# SAMV71_Xplained_Ultra_Memory.net
KiCad netlist of a schematic drawn in Altium Designer
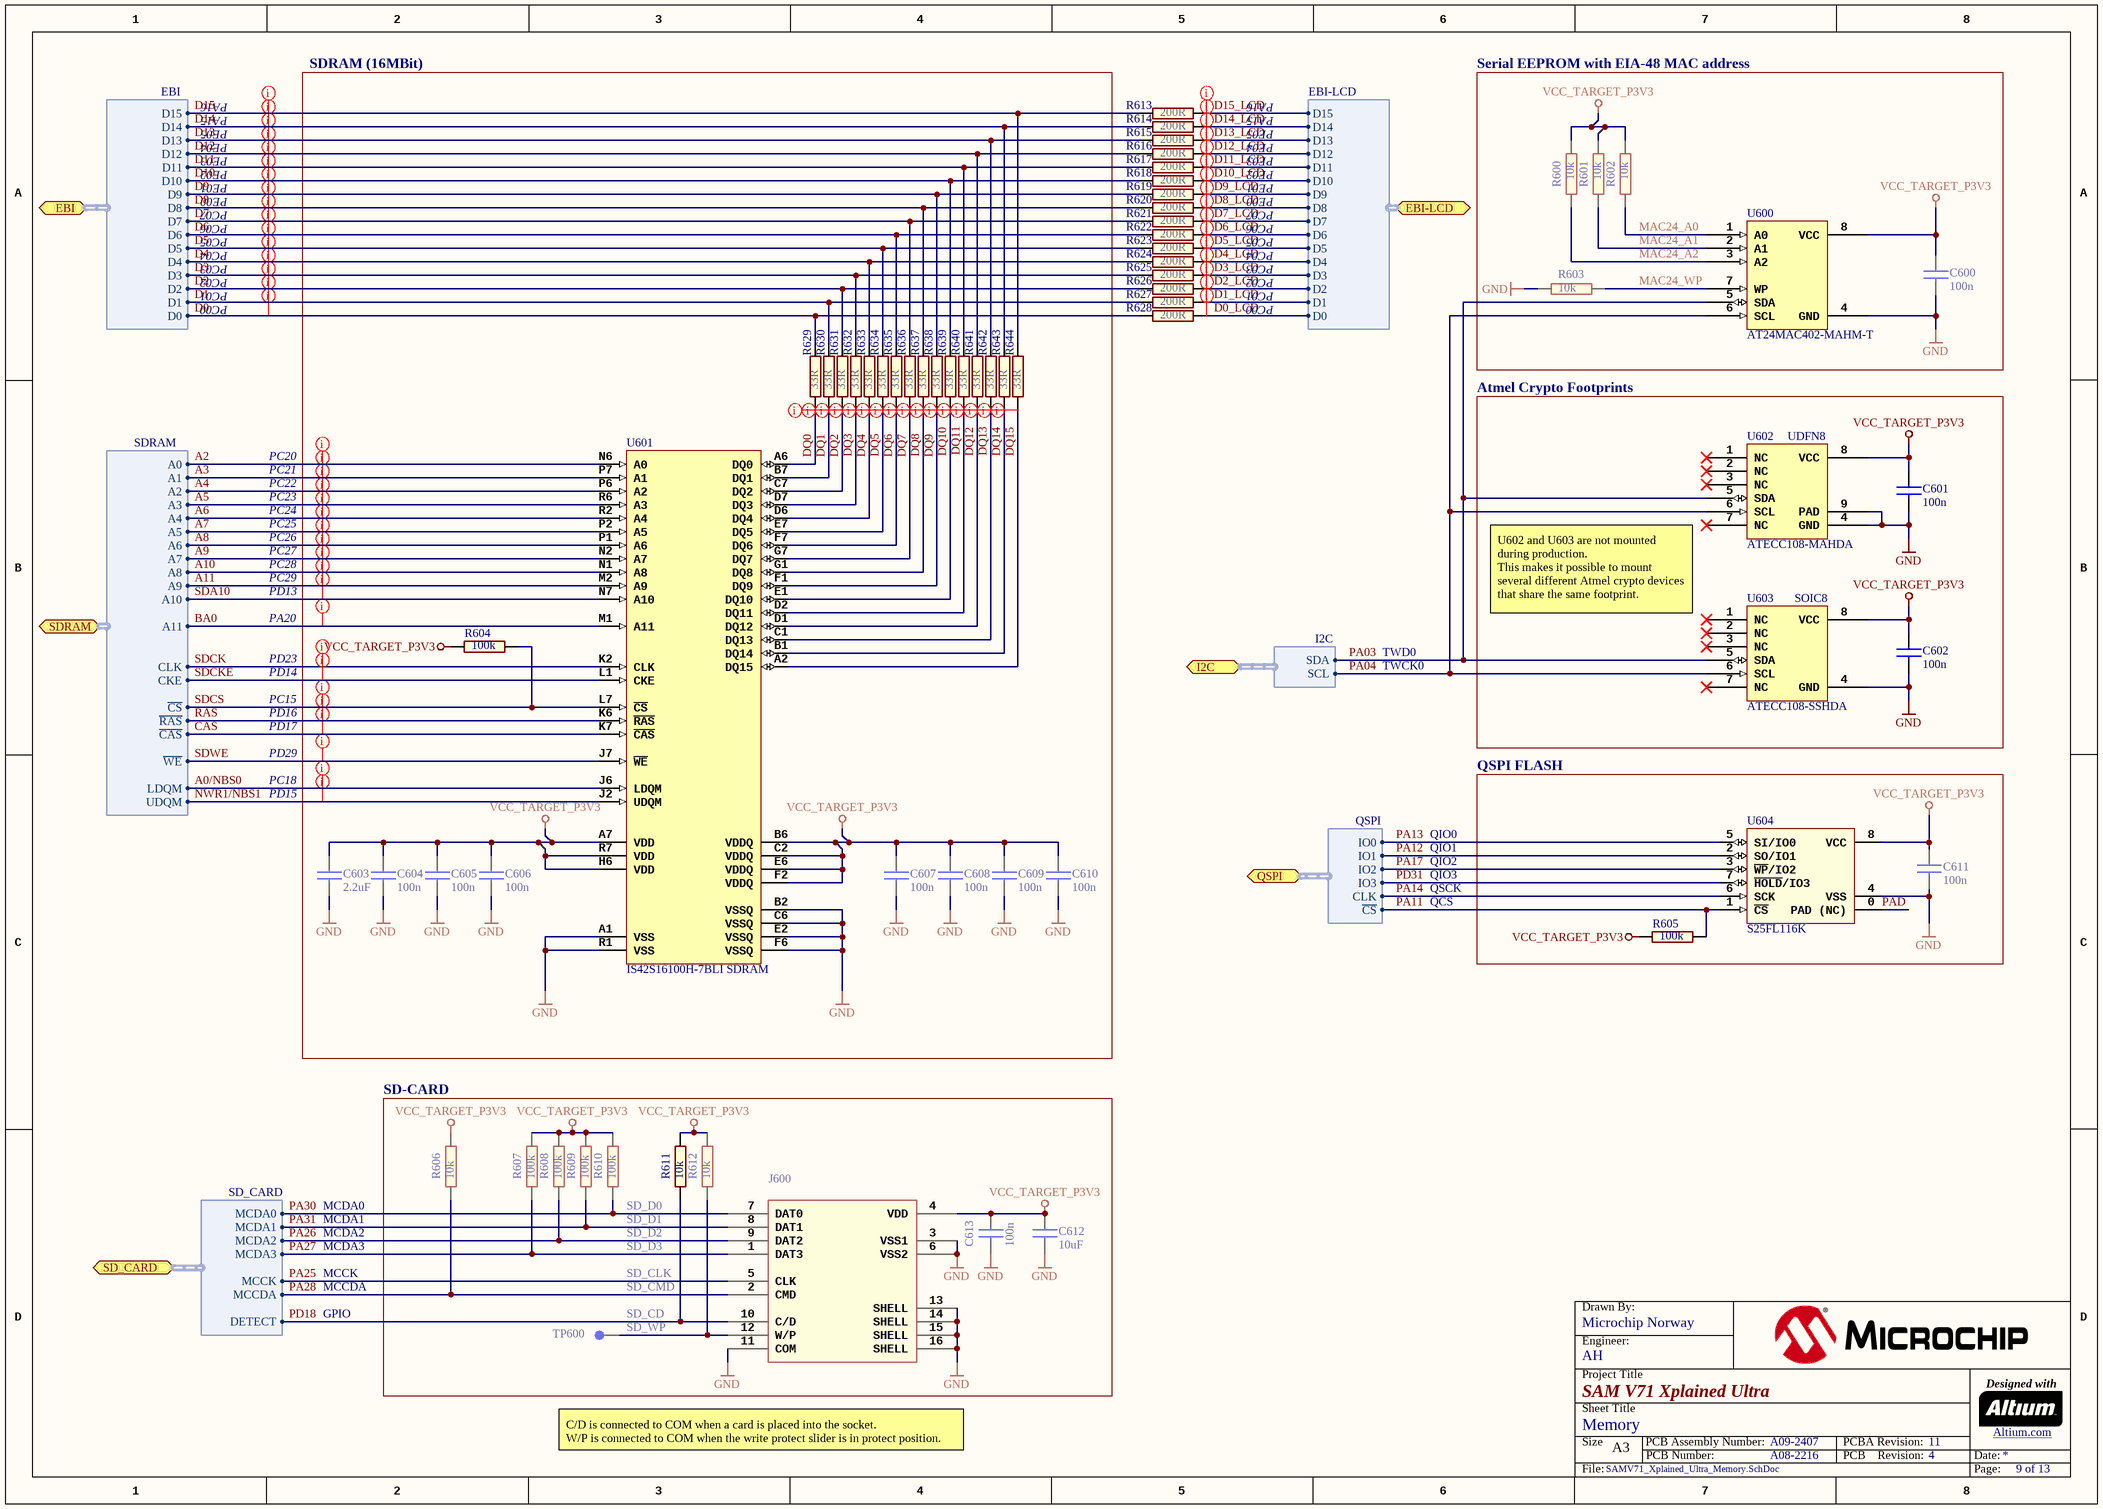
[diagram p0: SAMV71_Xplained_Ultra_Memory.SchDoc]

(export (version "E")
  (design (tool "Eeschema 10.0.6"))
  (components
    (comp (ref "C600")
      (value "100n")
      (footprint "AP1-00001")
      (description "Ceramic capacitor, SMD 0402, X7R, 16V, +/-10%")
      (fields (field (name "TOLERANCE") "16V, +/-10%") (field (name "MANUFACTURER") "Kemet"))
      (libsource (lib "AltiumDbLib") (part "CAP-NONPOL"))
    )
    (comp (ref "C601")
      (value "100n")
      (footprint "AP1-00001")
      (description "Ceramic capacitor, SMD 0402, X7R, 16V, +/-10%")
      (fields (field (name "TOLERANCE") "16V, +/-10%") (field (name "MANUFACTURER") "Kemet"))
      (libsource (lib "AltiumDbLib") (part "CAP-NONPOL"))
    )
    (comp (ref "C602")
      (value "100n")
      (footprint "AP1-00001")
      (description "Ceramic capacitor, SMD 0402, X7R, 16V, +/-10%")
      (fields (field (name "TOLERANCE") "16V, +/-10%") (field (name "MANUFACTURER") "Kemet"))
      (libsource (lib "AltiumDbLib") (part "CAP-NONPOL"))
    )
    (comp (ref "C603")
      (value "2.2uF")
      (footprint "AP1-00053")
      (description "Ceramic capacitor, SMD 0402, X5R, 6.3V, +/-20%")
      (fields (field (name "TOLERANCE") "Â±20%") (field (name "MANUFACTURER") "Kemet"))
      (libsource (lib "AltiumDbLib") (part "CAP-NONPOL"))
    )
    (comp (ref "C604")
      (value "100n")
      (footprint "AP1-00053")
      (description "Ceramic capacitor, SMD 0402, X7R, 16V, +/-10%")
      (fields (field (name "TOLERANCE") "16V, +/-10%") (field (name "MANUFACTURER") "Kemet"))
      (libsource (lib "AltiumDbLib") (part "CAP-NONPOL"))
    )
    (comp (ref "C605")
      (value "100n")
      (footprint "AP1-00053")
      (description "Ceramic capacitor, SMD 0402, X7R, 16V, +/-10%")
      (fields (field (name "TOLERANCE") "16V, +/-10%") (field (name "MANUFACTURER") "Kemet"))
      (libsource (lib "AltiumDbLib") (part "CAP-NONPOL"))
    )
    (comp (ref "C606")
      (value "100n")
      (footprint "AP1-00053")
      (description "Ceramic capacitor, SMD 0402, X7R, 16V, +/-10%")
      (fields (field (name "TOLERANCE") "16V, +/-10%") (field (name "MANUFACTURER") "Kemet"))
      (libsource (lib "AltiumDbLib") (part "CAP-NONPOL"))
    )
    (comp (ref "C607")
      (value "100n")
      (footprint "AP1-00053")
      (description "Ceramic capacitor, SMD 0402, X7R, 16V, +/-10%")
      (fields (field (name "TOLERANCE") "16V, +/-10%") (field (name "MANUFACTURER") "Kemet"))
      (libsource (lib "AltiumDbLib") (part "CAP-NONPOL"))
    )
    (comp (ref "C608")
      (value "100n")
      (footprint "AP1-00053")
      (description "Ceramic capacitor, SMD 0402, X7R, 16V, +/-10%")
      (fields (field (name "TOLERANCE") "16V, +/-10%") (field (name "MANUFACTURER") "Kemet"))
      (libsource (lib "AltiumDbLib") (part "CAP-NONPOL"))
    )
    (comp (ref "C609")
      (value "100n")
      (footprint "AP1-00053")
      (description "Ceramic capacitor, SMD 0402, X7R, 16V, +/-10%")
      (fields (field (name "TOLERANCE") "16V, +/-10%") (field (name "MANUFACTURER") "Kemet"))
      (libsource (lib "AltiumDbLib") (part "CAP-NONPOL"))
    )
    (comp (ref "C610")
      (value "100n")
      (footprint "AP1-00053")
      (description "Ceramic capacitor, SMD 0402, X7R, 16V, +/-10%")
      (fields (field (name "TOLERANCE") "16V, +/-10%") (field (name "MANUFACTURER") "Kemet"))
      (libsource (lib "AltiumDbLib") (part "CAP-NONPOL"))
    )
    (comp (ref "C611")
      (value "100n")
      (footprint "AP1-00001")
      (description "Ceramic capacitor, SMD 0402, X7R, 16V, +/-10%")
      (fields (field (name "TOLERANCE") "16V, +/-10%") (field (name "MANUFACTURER") "Kemet"))
      (libsource (lib "AltiumDbLib") (part "CAP-NONPOL"))
    )
    (comp (ref "C612")
      (value "10uF")
      (footprint "AP1-00041")
      (description "Ceramic capacitor, SMD 0805, X5R, 10V, 10 %, (de19441)")
      (fields (field (name "TOLERANCE") "10%") (field (name "MANUFACTURER") "Murata"))
      (libsource (lib "AltiumDbLib") (part "CAP-NONPOL"))
    )
    (comp (ref "C613")
      (value "100n")
      (footprint "AP1-00001")
      (description "Ceramic capacitor, SMD 0402, X7R, 16V, +/-10%")
      (fields (field (name "TOLERANCE") "16V, +/-10%") (field (name "MANUFACTURER") "Kemet"))
      (libsource (lib "AltiumDbLib") (part "CAP-NONPOL"))
    )
    (comp (ref "J600")
      (value "~")
      (footprint "AP8-00377")
      (description "SD/MMC socket, 2.7mm, push-push, SMD")
      (fields
        (field (name "MANUFACTURER") "Kyocera-elco")
        (field (name "MPN") "KYOCERA - 14 5738 009 220 859+")
      )
      (libsource (lib "AltiumDbLib") (part "SD_MMC"))
    )
    (comp (ref "R600")
      (value "10k")
      (footprint "AP2-00000")
      (description "Thick film resistor, SMD 0402, 1/16W, 1%")
      (fields (field (name "TOLERANCE") "1 %") (field (name "MANUFACTURER") "vishay"))
      (libsource (lib "AltiumDbLib") (part "R2"))
    )
    (comp (ref "R601")
      (value "10k")
      (footprint "AP2-00000")
      (description "Thick film resistor, SMD 0402, 1/16W, 1%")
      (fields (field (name "TOLERANCE") "1 %") (field (name "MANUFACTURER") "vishay"))
      (libsource (lib "AltiumDbLib") (part "R2"))
    )
    (comp (ref "R602")
      (value "10k")
      (footprint "AP2-00000")
      (description "Thick film resistor, SMD 0402, 1/16W, 1%")
      (fields (field (name "TOLERANCE") "1 %") (field (name "MANUFACTURER") "vishay"))
      (libsource (lib "AltiumDbLib") (part "R2"))
    )
    (comp (ref "R603")
      (value "10k")
      (footprint "AP2-00000")
      (description "Thick film resistor, SMD 0402, 1/16W, 1%")
      (fields (field (name "TOLERANCE") "1 %") (field (name "MANUFACTURER") "vishay"))
      (libsource (lib "") (part "R2_1"))
    )
    (comp (ref "R604")
      (value "100k")
      (footprint "AP2-00000")
      (description "Thick film resistor, SMD 0402, 1/16W, 1%")
      (fields (field (name "TOLERANCE") "1 %") (field (name "MANUFACTURER") "ASJ"))
      (libsource (lib "") (part "R2_1"))
    )
    (comp (ref "R605")
      (value "100k")
      (footprint "AP2-00000")
      (description "Thick film resistor, SMD 0402, 1/16W, 1%")
      (fields (field (name "TOLERANCE") "1 %") (field (name "MANUFACTURER") "ASJ"))
      (libsource (lib "") (part "R2_1"))
    )
    (comp (ref "R606")
      (value "10k")
      (footprint "AP2-00000")
      (description "Thick film resistor, SMD 0402, 1/16W, 1%")
      (fields (field (name "TOLERANCE") "1 %") (field (name "MANUFACTURER") "vishay"))
      (libsource (lib "AltiumDbLib") (part "R2"))
    )
    (comp (ref "R607")
      (value "100k")
      (footprint "AP2-00000")
      (description "Thick film resistor, SMD 0402, 1/16W, 1%")
      (fields (field (name "TOLERANCE") "1 %") (field (name "MANUFACTURER") "ASJ"))
      (libsource (lib "AltiumDbLib") (part "R2"))
    )
    (comp (ref "R608")
      (value "100k")
      (footprint "AP2-00000")
      (description "Thick film resistor, SMD 0402, 1/16W, 1%")
      (fields (field (name "TOLERANCE") "1 %") (field (name "MANUFACTURER") "ASJ"))
      (libsource (lib "AltiumDbLib") (part "R2"))
    )
    (comp (ref "R609")
      (value "100k")
      (footprint "AP2-00000")
      (description "Thick film resistor, SMD 0402, 1/16W, 1%")
      (fields (field (name "TOLERANCE") "1 %") (field (name "MANUFACTURER") "ASJ"))
      (libsource (lib "AltiumDbLib") (part "R2"))
    )
    (comp (ref "R610")
      (value "100k")
      (footprint "AP2-00000")
      (description "Thick film resistor, SMD 0402, 1/16W, 1%")
      (fields (field (name "TOLERANCE") "1 %") (field (name "MANUFACTURER") "ASJ"))
      (libsource (lib "AltiumDbLib") (part "R2"))
    )
    (comp (ref "R611")
      (value "10k")
      (footprint "AP2-00000")
      (description "Thick film resistor, SMD 0402, 1/16W, 1%")
      (fields (field (name "TOLERANCE") "1 %") (field (name "MANUFACTURER") "vishay"))
      (libsource (lib "AltiumDbLib") (part "R2"))
    )
    (comp (ref "R612")
      (value "10k")
      (footprint "AP2-00000")
      (description "Thick film resistor, SMD 0402, 1/16W, 1%")
      (fields (field (name "TOLERANCE") "1 %") (field (name "MANUFACTURER") "vishay"))
      (libsource (lib "AltiumDbLib") (part "R2"))
    )
    (comp (ref "R613")
      (value "200R")
      (footprint "AP2-00011")
      (description "Thick film resistor, SMD 0402, 1/16W, 1%")
      (fields (field (name "TOLERANCE") "1 %"))
      (libsource (lib "") (part "R2_3"))
    )
    (comp (ref "R614")
      (value "200R")
      (footprint "AP2-00011")
      (description "Thick film resistor, SMD 0402, 1/16W, 1%")
      (fields (field (name "TOLERANCE") "1 %"))
      (libsource (lib "") (part "R2_3"))
    )
    (comp (ref "R615")
      (value "200R")
      (footprint "AP2-00011")
      (description "Thick film resistor, SMD 0402, 1/16W, 1%")
      (fields (field (name "TOLERANCE") "1 %"))
      (libsource (lib "") (part "R2_3"))
    )
    (comp (ref "R616")
      (value "200R")
      (footprint "AP2-00011")
      (description "Thick film resistor, SMD 0402, 1/16W, 1%")
      (fields (field (name "TOLERANCE") "1 %"))
      (libsource (lib "") (part "R2_3"))
    )
    (comp (ref "R617")
      (value "200R")
      (footprint "AP2-00011")
      (description "Thick film resistor, SMD 0402, 1/16W, 1%")
      (fields (field (name "TOLERANCE") "1 %"))
      (libsource (lib "") (part "R2_3"))
    )
    (comp (ref "R618")
      (value "200R")
      (footprint "AP2-00011")
      (description "Thick film resistor, SMD 0402, 1/16W, 1%")
      (fields (field (name "TOLERANCE") "1 %"))
      (libsource (lib "") (part "R2_3"))
    )
    (comp (ref "R619")
      (value "200R")
      (footprint "AP2-00011")
      (description "Thick film resistor, SMD 0402, 1/16W, 1%")
      (fields (field (name "TOLERANCE") "1 %"))
      (libsource (lib "") (part "R2_3"))
    )
    (comp (ref "R620")
      (value "200R")
      (footprint "AP2-00011")
      (description "Thick film resistor, SMD 0402, 1/16W, 1%")
      (fields (field (name "TOLERANCE") "1 %"))
      (libsource (lib "") (part "R2_3"))
    )
    (comp (ref "R621")
      (value "200R")
      (footprint "AP2-00011")
      (description "Thick film resistor, SMD 0402, 1/16W, 1%")
      (fields (field (name "TOLERANCE") "1 %"))
      (libsource (lib "") (part "R2_3"))
    )
    (comp (ref "R622")
      (value "200R")
      (footprint "AP2-00011")
      (description "Thick film resistor, SMD 0402, 1/16W, 1%")
      (fields (field (name "TOLERANCE") "1 %"))
      (libsource (lib "") (part "R2_3"))
    )
    (comp (ref "R623")
      (value "200R")
      (footprint "AP2-00011")
      (description "Thick film resistor, SMD 0402, 1/16W, 1%")
      (fields (field (name "TOLERANCE") "1 %"))
      (libsource (lib "") (part "R2_3"))
    )
    (comp (ref "R624")
      (value "200R")
      (footprint "AP2-00011")
      (description "Thick film resistor, SMD 0402, 1/16W, 1%")
      (fields (field (name "TOLERANCE") "1 %"))
      (libsource (lib "") (part "R2_3"))
    )
    (comp (ref "R625")
      (value "200R")
      (footprint "AP2-00011")
      (description "Thick film resistor, SMD 0402, 1/16W, 1%")
      (fields (field (name "TOLERANCE") "1 %"))
      (libsource (lib "") (part "R2_3"))
    )
    (comp (ref "R626")
      (value "200R")
      (footprint "AP2-00011")
      (description "Thick film resistor, SMD 0402, 1/16W, 1%")
      (fields (field (name "TOLERANCE") "1 %"))
      (libsource (lib "") (part "R2_3"))
    )
    (comp (ref "R627")
      (value "200R")
      (footprint "AP2-00011")
      (description "Thick film resistor, SMD 0402, 1/16W, 1%")
      (fields (field (name "TOLERANCE") "1 %"))
      (libsource (lib "") (part "R2_3"))
    )
    (comp (ref "R628")
      (value "200R")
      (footprint "AP2-00011")
      (description "Thick film resistor, SMD 0402, 1/16W, 1%")
      (fields (field (name "TOLERANCE") "1 %"))
      (libsource (lib "") (part "R2_3"))
    )
    (comp (ref "R629")
      (value "33R")
      (footprint "AP2-00011")
      (description "Thick film resistor, SMD 0402, 1/16W, 1%")
      (fields (field (name "TOLERANCE") "1 %") (field (name "MANUFACTURER") "ASJ"))
      (libsource (lib "") (part "R2_2"))
    )
    (comp (ref "R630")
      (value "33R")
      (footprint "AP2-00011")
      (description "Thick film resistor, SMD 0402, 1/16W, 1%")
      (fields (field (name "TOLERANCE") "1 %") (field (name "MANUFACTURER") "ASJ"))
      (libsource (lib "") (part "R2_2"))
    )
    (comp (ref "R631")
      (value "33R")
      (footprint "AP2-00011")
      (description "Thick film resistor, SMD 0402, 1/16W, 1%")
      (fields (field (name "TOLERANCE") "1 %") (field (name "MANUFACTURER") "ASJ"))
      (libsource (lib "") (part "R2_2"))
    )
    (comp (ref "R632")
      (value "33R")
      (footprint "AP2-00011")
      (description "Thick film resistor, SMD 0402, 1/16W, 1%")
      (fields (field (name "TOLERANCE") "1 %") (field (name "MANUFACTURER") "ASJ"))
      (libsource (lib "") (part "R2_2"))
    )
    (comp (ref "R633")
      (value "33R")
      (footprint "AP2-00011")
      (description "Thick film resistor, SMD 0402, 1/16W, 1%")
      (fields (field (name "TOLERANCE") "1 %") (field (name "MANUFACTURER") "ASJ"))
      (libsource (lib "") (part "R2_2"))
    )
    (comp (ref "R634")
      (value "33R")
      (footprint "AP2-00011")
      (description "Thick film resistor, SMD 0402, 1/16W, 1%")
      (fields (field (name "TOLERANCE") "1 %") (field (name "MANUFACTURER") "ASJ"))
      (libsource (lib "") (part "R2_2"))
    )
    (comp (ref "R635")
      (value "33R")
      (footprint "AP2-00011")
      (description "Thick film resistor, SMD 0402, 1/16W, 1%")
      (fields (field (name "TOLERANCE") "1 %") (field (name "MANUFACTURER") "ASJ"))
      (libsource (lib "") (part "R2_2"))
    )
    (comp (ref "R636")
      (value "33R")
      (footprint "AP2-00011")
      (description "Thick film resistor, SMD 0402, 1/16W, 1%")
      (fields (field (name "TOLERANCE") "1 %") (field (name "MANUFACTURER") "ASJ"))
      (libsource (lib "") (part "R2_2"))
    )
    (comp (ref "R637")
      (value "33R")
      (footprint "AP2-00011")
      (description "Thick film resistor, SMD 0402, 1/16W, 1%")
      (fields (field (name "TOLERANCE") "1 %") (field (name "MANUFACTURER") "ASJ"))
      (libsource (lib "") (part "R2_2"))
    )
    (comp (ref "R638")
      (value "33R")
      (footprint "AP2-00011")
      (description "Thick film resistor, SMD 0402, 1/16W, 1%")
      (fields (field (name "TOLERANCE") "1 %") (field (name "MANUFACTURER") "ASJ"))
      (libsource (lib "") (part "R2_2"))
    )
    (comp (ref "R639")
      (value "33R")
      (footprint "AP2-00011")
      (description "Thick film resistor, SMD 0402, 1/16W, 1%")
      (fields (field (name "TOLERANCE") "1 %") (field (name "MANUFACTURER") "ASJ"))
      (libsource (lib "") (part "R2_2"))
    )
    (comp (ref "R640")
      (value "33R")
      (footprint "AP2-00011")
      (description "Thick film resistor, SMD 0402, 1/16W, 1%")
      (fields (field (name "TOLERANCE") "1 %") (field (name "MANUFACTURER") "ASJ"))
      (libsource (lib "") (part "R2_2"))
    )
    (comp (ref "R641")
      (value "33R")
      (footprint "AP2-00011")
      (description "Thick film resistor, SMD 0402, 1/16W, 1%")
      (fields (field (name "TOLERANCE") "1 %") (field (name "MANUFACTURER") "ASJ"))
      (libsource (lib "") (part "R2_2"))
    )
    (comp (ref "R642")
      (value "33R")
      (footprint "AP2-00011")
      (description "Thick film resistor, SMD 0402, 1/16W, 1%")
      (fields (field (name "TOLERANCE") "1 %") (field (name "MANUFACTURER") "ASJ"))
      (libsource (lib "") (part "R2_2"))
    )
    (comp (ref "R643")
      (value "33R")
      (footprint "AP2-00011")
      (description "Thick film resistor, SMD 0402, 1/16W, 1%")
      (fields (field (name "TOLERANCE") "1 %") (field (name "MANUFACTURER") "ASJ"))
      (libsource (lib "") (part "R2_2"))
    )
    (comp (ref "R644")
      (value "33R")
      (footprint "AP2-00011")
      (description "Thick film resistor, SMD 0402, 1/16W, 1%")
      (fields (field (name "TOLERANCE") "1 %") (field (name "MANUFACTURER") "ASJ"))
      (libsource (lib "") (part "R2_2"))
    )
    (comp (ref "TP600")
      (value "~")
      (footprint "AP8-00010")
      (description "Single SMD testpad")
      (libsource (lib "AltiumDbLib") (part "TESTPOINT"))
    )
    (comp (ref "U600")
      (value "AT24MAC402-MAHM-T")
      (footprint "AP6-00186")
      (description "2kbit I2C EEPROM, single EUI-48 MAC, 1.7-5.5V, 2x3mm UDFN (8MA2)")
      (fields (field (name "MANUFACTURER") "ATMEL"))
      (libsource (lib "AltiumDbLib") (part "AT24MAC-8PIN"))
    )
    (comp (ref "U601")
      (value "IS42S16100H-7BLI SDRAM")
      (footprint "AP6-00400")
      (description "16Mbit  SDRAM (512K Words x 16 Bits x 2 Banks), 143 MHz 3,3V")
      (fields (field (name "MANUFACTURER") "ISSI") (field (name "MPN") "IS42S16100H-7BLI"))
      (libsource (lib "AltiumDbLib") (part "IS42S16100E"))
    )
    (comp (ref "U602")
      (value "ATECC108-MAHDA")
      (footprint "AP6-00409")
      (description "Secure authentication and product validation device, EEPROM, I2C, 2.0 - 5.5V, UDFN8")
      (fields (field (name "MANUFACTURER") "ATMEL") (field (name "MPN") "ATECC108-MAHDA-T"))
      (libsource (lib "AltiumDbLib") (part "ATECC108_UDFN"))
    )
    (comp (ref "U603")
      (value "ATECC108-SSHDA")
      (footprint "AP6-00071")
      (description "Secure authentication and product validation device, EEPROM, I2C, 2.0 - 5.5V, SOIC8")
      (fields (field (name "MANUFACTURER") "ATMEL") (field (name "MPN") "ATECC108-SSHDA-T"))
      (libsource (lib "AltiumDbLib") (part "ATECC108_SOIC"))
    )
    (comp (ref "U604")
      (value "S25FL116K")
      (footprint "AP6-00402")
      (description "16 Mbit (2MB) SPI Quad I/O flash, 3.3V, 108MHz, WSON-8, industrial temperature")
      (fields (field (name "MANUFACTURER") "Spansion") (field (name "MPN") "S25FL116K0XNFI013"))
      (libsource (lib "AltiumDbLib") (part "S25FL1"))
    )
  )
  (nets
    (net (code "7") (name "/A0{slash}NBS0") (class "Default")
      (node (ref "U601") (pin "J6") (pinfunction "LDQM_J6") (pintype "input"))
    )
    (net (code "8") (name "/A2") (class "Default")
      (node (ref "U601") (pin "N6") (pinfunction "A0_N6") (pintype "input"))
    )
    (net (code "9") (name "/A3") (class "Default")
      (node (ref "U601") (pin "P7") (pinfunction "A1_P7") (pintype "input"))
    )
    (net (code "10") (name "/A4") (class "Default")
      (node (ref "U601") (pin "P6") (pinfunction "A2_P6") (pintype "input"))
    )
    (net (code "11") (name "/A5") (class "Default")
      (node (ref "U601") (pin "R6") (pinfunction "A3_R6") (pintype "input"))
    )
    (net (code "12") (name "/A6") (class "Default")
      (node (ref "U601") (pin "R2") (pinfunction "A4_R2") (pintype "input"))
    )
    (net (code "13") (name "/A7") (class "Default")
      (node (ref "U601") (pin "P2") (pinfunction "A5_P2") (pintype "input"))
    )
    (net (code "14") (name "/A8") (class "Default")
      (node (ref "U601") (pin "P1") (pinfunction "A6_P1") (pintype "input"))
    )
    (net (code "15") (name "/A9") (class "Default")
      (node (ref "U601") (pin "N2") (pinfunction "A7_N2") (pintype "input"))
    )
    (net (code "16") (name "/A10") (class "Default")
      (node (ref "U601") (pin "N1") (pinfunction "A8_N1") (pintype "input"))
    )
    (net (code "17") (name "/A11") (class "Default")
      (node (ref "U601") (pin "M2") (pinfunction "A9_M2") (pintype "input"))
    )
    (net (code "18") (name "/BA0") (class "Default")
      (node (ref "U601") (pin "M1") (pinfunction "A11_M1") (pintype "input"))
    )
    (net (code "19") (name "/CAS") (class "Default")
      (node (ref "U601") (pin "K7") (pinfunction "~{CAS}_K7") (pintype "input"))
    )
    (net (code "20") (name "/D0") (class "Default")
      (node (ref "R628") (pin "2") (pinfunction "2_2") (pintype "passive"))
      (node (ref "R629") (pin "1") (pinfunction "1_1") (pintype "passive"))
    )
    (net (code "21") (name "/D0_LCD") (class "Default")
      (node (ref "R628") (pin "1") (pinfunction "1_1") (pintype "passive"))
    )
    (net (code "22") (name "/D1") (class "Default")
      (node (ref "R627") (pin "2") (pinfunction "2_2") (pintype "passive"))
      (node (ref "R630") (pin "1") (pinfunction "1_1") (pintype "passive"))
    )
    (net (code "23") (name "/D1_LCD") (class "Default")
      (node (ref "R627") (pin "1") (pinfunction "1_1") (pintype "passive"))
    )
    (net (code "24") (name "/D2") (class "Default")
      (node (ref "R626") (pin "2") (pinfunction "2_2") (pintype "passive"))
      (node (ref "R631") (pin "1") (pinfunction "1_1") (pintype "passive"))
    )
    (net (code "25") (name "/D2_LCD") (class "Default")
      (node (ref "R626") (pin "1") (pinfunction "1_1") (pintype "passive"))
    )
    (net (code "26") (name "/D3") (class "Default")
      (node (ref "R625") (pin "2") (pinfunction "2_2") (pintype "passive"))
      (node (ref "R632") (pin "1") (pinfunction "1_1") (pintype "passive"))
    )
    (net (code "27") (name "/D3_LCD") (class "Default")
      (node (ref "R625") (pin "1") (pinfunction "1_1") (pintype "passive"))
    )
    (net (code "28") (name "/D4") (class "Default")
      (node (ref "R624") (pin "2") (pinfunction "2_2") (pintype "passive"))
      (node (ref "R633") (pin "1") (pinfunction "1_1") (pintype "passive"))
    )
    (net (code "29") (name "/D4_LCD") (class "Default")
      (node (ref "R624") (pin "1") (pinfunction "1_1") (pintype "passive"))
    )
    (net (code "30") (name "/D5") (class "Default")
      (node (ref "R623") (pin "2") (pinfunction "2_2") (pintype "passive"))
      (node (ref "R634") (pin "1") (pinfunction "1_1") (pintype "passive"))
    )
    (net (code "31") (name "/D5_LCD") (class "Default")
      (node (ref "R623") (pin "1") (pinfunction "1_1") (pintype "passive"))
    )
    (net (code "32") (name "/D6") (class "Default")
      (node (ref "R622") (pin "2") (pinfunction "2_2") (pintype "passive"))
      (node (ref "R635") (pin "1") (pinfunction "1_1") (pintype "passive"))
    )
    (net (code "33") (name "/D6_LCD") (class "Default")
      (node (ref "R622") (pin "1") (pinfunction "1_1") (pintype "passive"))
    )
    (net (code "34") (name "/D7") (class "Default")
      (node (ref "R621") (pin "2") (pinfunction "2_2") (pintype "passive"))
      (node (ref "R636") (pin "1") (pinfunction "1_1") (pintype "passive"))
    )
    (net (code "35") (name "/D7_LCD") (class "Default")
      (node (ref "R621") (pin "1") (pinfunction "1_1") (pintype "passive"))
    )
    (net (code "36") (name "/D8") (class "Default")
      (node (ref "R620") (pin "2") (pinfunction "2_2") (pintype "passive"))
      (node (ref "R637") (pin "1") (pinfunction "1_1") (pintype "passive"))
    )
    (net (code "37") (name "/D8_LCD") (class "Default")
      (node (ref "R620") (pin "1") (pinfunction "1_1") (pintype "passive"))
    )
    (net (code "38") (name "/D9") (class "Default")
      (node (ref "R619") (pin "2") (pinfunction "2_2") (pintype "passive"))
      (node (ref "R638") (pin "1") (pinfunction "1_1") (pintype "passive"))
    )
    (net (code "39") (name "/D9_LCD") (class "Default")
      (node (ref "R619") (pin "1") (pinfunction "1_1") (pintype "passive"))
    )
    (net (code "40") (name "/D10") (class "Default")
      (node (ref "R618") (pin "2") (pinfunction "2_2") (pintype "passive"))
      (node (ref "R639") (pin "1") (pinfunction "1_1") (pintype "passive"))
    )
    (net (code "41") (name "/D10_LCD") (class "Default")
      (node (ref "R618") (pin "1") (pinfunction "1_1") (pintype "passive"))
    )
    (net (code "42") (name "/D11") (class "Default")
      (node (ref "R617") (pin "2") (pinfunction "2_2") (pintype "passive"))
      (node (ref "R640") (pin "1") (pinfunction "1_1") (pintype "passive"))
    )
    (net (code "43") (name "/D11_LCD") (class "Default")
      (node (ref "R617") (pin "1") (pinfunction "1_1") (pintype "passive"))
    )
    (net (code "44") (name "/D12") (class "Default")
      (node (ref "R616") (pin "2") (pinfunction "2_2") (pintype "passive"))
      (node (ref "R641") (pin "1") (pinfunction "1_1") (pintype "passive"))
    )
    (net (code "45") (name "/D12_LCD") (class "Default")
      (node (ref "R616") (pin "1") (pinfunction "1_1") (pintype "passive"))
    )
    (net (code "46") (name "/D13") (class "Default")
      (node (ref "R615") (pin "2") (pinfunction "2_2") (pintype "passive"))
      (node (ref "R642") (pin "1") (pinfunction "1_1") (pintype "passive"))
    )
    (net (code "47") (name "/D13_LCD") (class "Default")
      (node (ref "R615") (pin "1") (pinfunction "1_1") (pintype "passive"))
    )
    (net (code "48") (name "/D14") (class "Default")
      (node (ref "R614") (pin "2") (pinfunction "2_2") (pintype "passive"))
      (node (ref "R643") (pin "1") (pinfunction "1_1") (pintype "passive"))
    )
    (net (code "49") (name "/D14_LCD") (class "Default")
      (node (ref "R614") (pin "1") (pinfunction "1_1") (pintype "passive"))
    )
    (net (code "50") (name "/D15") (class "Default")
      (node (ref "R613") (pin "2") (pinfunction "2_2") (pintype "passive"))
      (node (ref "R644") (pin "1") (pinfunction "1_1") (pintype "passive"))
    )
    (net (code "51") (name "/D15_LCD") (class "Default")
      (node (ref "R613") (pin "1") (pinfunction "1_1") (pintype "passive"))
    )
    (net (code "52") (name "/DQ0") (class "Default")
      (node (ref "R629") (pin "2") (pinfunction "2_2") (pintype "passive"))
      (node (ref "U601") (pin "A6") (pinfunction "DQ0_A6") (pintype "bidirectional"))
    )
    (net (code "53") (name "/DQ1") (class "Default")
      (node (ref "R630") (pin "2") (pinfunction "2_2") (pintype "passive"))
      (node (ref "U601") (pin "B7") (pinfunction "DQ1_B7") (pintype "bidirectional"))
    )
    (net (code "54") (name "/DQ2") (class "Default")
      (node (ref "R631") (pin "2") (pinfunction "2_2") (pintype "passive"))
      (node (ref "U601") (pin "C7") (pinfunction "DQ2_C7") (pintype "bidirectional"))
    )
    (net (code "55") (name "/DQ3") (class "Default")
      (node (ref "R632") (pin "2") (pinfunction "2_2") (pintype "passive"))
      (node (ref "U601") (pin "D7") (pinfunction "DQ3_D7") (pintype "bidirectional"))
    )
    (net (code "56") (name "/DQ4") (class "Default")
      (node (ref "R633") (pin "2") (pinfunction "2_2") (pintype "passive"))
      (node (ref "U601") (pin "D6") (pinfunction "DQ4_D6") (pintype "bidirectional"))
    )
    (net (code "57") (name "/DQ5") (class "Default")
      (node (ref "R634") (pin "2") (pinfunction "2_2") (pintype "passive"))
      (node (ref "U601") (pin "E7") (pinfunction "DQ5_E7") (pintype "bidirectional"))
    )
    (net (code "58") (name "/DQ6") (class "Default")
      (node (ref "R635") (pin "2") (pinfunction "2_2") (pintype "passive"))
      (node (ref "U601") (pin "F7") (pinfunction "DQ6_F7") (pintype "bidirectional"))
    )
    (net (code "59") (name "/DQ7") (class "Default")
      (node (ref "R636") (pin "2") (pinfunction "2_2") (pintype "passive"))
      (node (ref "U601") (pin "G7") (pinfunction "DQ7_G7") (pintype "bidirectional"))
    )
    (net (code "60") (name "/DQ8") (class "Default")
      (node (ref "R637") (pin "2") (pinfunction "2_2") (pintype "passive"))
      (node (ref "U601") (pin "G1") (pinfunction "DQ8_G1") (pintype "bidirectional"))
    )
    (net (code "61") (name "/DQ9") (class "Default")
      (node (ref "R638") (pin "2") (pinfunction "2_2") (pintype "passive"))
      (node (ref "U601") (pin "F1") (pinfunction "DQ9_F1") (pintype "bidirectional"))
    )
    (net (code "62") (name "/DQ10") (class "Default")
      (node (ref "R639") (pin "2") (pinfunction "2_2") (pintype "passive"))
      (node (ref "U601") (pin "E1") (pinfunction "DQ10_E1") (pintype "bidirectional"))
    )
    (net (code "63") (name "/DQ11") (class "Default")
      (node (ref "R640") (pin "2") (pinfunction "2_2") (pintype "passive"))
      (node (ref "U601") (pin "D2") (pinfunction "DQ11_D2") (pintype "bidirectional"))
    )
    (net (code "64") (name "/DQ12") (class "Default")
      (node (ref "R641") (pin "2") (pinfunction "2_2") (pintype "passive"))
      (node (ref "U601") (pin "D1") (pinfunction "DQ12_D1") (pintype "bidirectional"))
    )
    (net (code "65") (name "/DQ13") (class "Default")
      (node (ref "R642") (pin "2") (pinfunction "2_2") (pintype "passive"))
      (node (ref "U601") (pin "C1") (pinfunction "DQ13_C1") (pintype "bidirectional"))
    )
    (net (code "66") (name "/DQ14") (class "Default")
      (node (ref "R643") (pin "2") (pinfunction "2_2") (pintype "passive"))
      (node (ref "U601") (pin "B1") (pinfunction "DQ14_B1") (pintype "bidirectional"))
    )
    (net (code "67") (name "/DQ15") (class "Default")
      (node (ref "R644") (pin "2") (pinfunction "2_2") (pintype "passive"))
      (node (ref "U601") (pin "A2") (pinfunction "DQ15_A2") (pintype "bidirectional"))
    )
    (net (code "68") (name "/MAC24_A0") (class "Default")
      (node (ref "R602") (pin "1") (pinfunction "1_1") (pintype "passive"))
      (node (ref "U600") (pin "1") (pinfunction "A0_1") (pintype "input"))
    )
    (net (code "69") (name "/MAC24_A1") (class "Default")
      (node (ref "R601") (pin "1") (pinfunction "1_1") (pintype "passive"))
      (node (ref "U600") (pin "2") (pinfunction "A1_2") (pintype "input"))
    )
    (net (code "70") (name "/MAC24_A2") (class "Default")
      (node (ref "R600") (pin "1") (pinfunction "1_1") (pintype "passive"))
      (node (ref "U600") (pin "3") (pinfunction "A2_3") (pintype "input"))
    )
    (net (code "71") (name "/MAC24_WP") (class "Default")
      (node (ref "R603") (pin "2") (pinfunction "2_2") (pintype "passive"))
      (node (ref "U600") (pin "7") (pinfunction "WP_7") (pintype "input"))
    )
    (net (code "72") (name "/NWR1{slash}NBS1") (class "Default")
      (node (ref "U601") (pin "J2") (pinfunction "UDQM_J2") (pintype "input"))
    )
    (net (code "73") (name "/PA03") (class "Default")
      (node (ref "U600") (pin "5") (pinfunction "SDA_5") (pintype "bidirectional"))
      (node (ref "U602") (pin "5") (pinfunction "SDA_5") (pintype "bidirectional"))
      (node (ref "U603") (pin "5") (pinfunction "SDA_5") (pintype "bidirectional"))
    )
    (net (code "74") (name "/PA04") (class "Default")
      (node (ref "U600") (pin "6") (pinfunction "SCL_6") (pintype "input"))
      (node (ref "U602") (pin "6") (pinfunction "SCL_6") (pintype "input"))
      (node (ref "U603") (pin "6") (pinfunction "SCL_6") (pintype "input"))
    )
    (net (code "75") (name "/PA11") (class "Default")
      (node (ref "R605") (pin "2") (pinfunction "2_2") (pintype "passive"))
      (node (ref "U604") (pin "1") (pinfunction "~{CS}_1") (pintype "input"))
    )
    (net (code "76") (name "/PA12") (class "Default")
      (node (ref "U604") (pin "2") (pinfunction "SO/IO1_2") (pintype "bidirectional"))
    )
    (net (code "77") (name "/PA13") (class "Default")
      (node (ref "U604") (pin "5") (pinfunction "SI/IO0_5") (pintype "bidirectional"))
    )
    (net (code "78") (name "/PA14") (class "Default")
      (node (ref "U604") (pin "6") (pinfunction "SCK_6") (pintype "input"))
    )
    (net (code "79") (name "/PA17") (class "Default")
      (node (ref "U604") (pin "3") (pinfunction "~{WP}/IO2_3") (pintype "bidirectional"))
    )
    (net (code "80") (name "/PA25") (class "Default")
      (node (ref "J600") (pin "5") (pinfunction "CLK_5") (pintype "passive"))
    )
    (net (code "81") (name "/PA26") (class "Default")
      (node (ref "J600") (pin "9") (pinfunction "DAT2_9") (pintype "passive"))
      (node (ref "R608") (pin "1") (pinfunction "1_1") (pintype "passive"))
    )
    (net (code "82") (name "/PA27") (class "Default")
      (node (ref "J600") (pin "1") (pinfunction "DAT3_1") (pintype "passive"))
      (node (ref "R607") (pin "1") (pinfunction "1_1") (pintype "passive"))
    )
    (net (code "83") (name "/PA28") (class "Default")
      (node (ref "J600") (pin "2") (pinfunction "CMD_2") (pintype "passive"))
      (node (ref "R606") (pin "1") (pinfunction "1_1") (pintype "passive"))
    )
    (net (code "84") (name "/PA30") (class "Default")
      (node (ref "J600") (pin "7") (pinfunction "DAT0_7") (pintype "passive"))
      (node (ref "R610") (pin "1") (pinfunction "1_1") (pintype "passive"))
    )
    (net (code "85") (name "/PA31") (class "Default")
      (node (ref "J600") (pin "8") (pinfunction "DAT1_8") (pintype "passive"))
      (node (ref "R609") (pin "1") (pinfunction "1_1") (pintype "passive"))
    )
    (net (code "86") (name "/PAD") (class "Default")
      (node (ref "U604") (pin "0") (pinfunction "PAD_(NC)_0") (pintype "power_in"))
    )
    (net (code "87") (name "/PD18") (class "Default")
      (node (ref "J600") (pin "10") (pinfunction "C/D_10") (pintype "passive"))
      (node (ref "R611") (pin "1") (pinfunction "1_1") (pintype "passive"))
    )
    (net (code "88") (name "/PD31") (class "Default")
      (node (ref "U604") (pin "7") (pinfunction "~{HOLD}/IO3_7") (pintype "bidirectional"))
    )
    (net (code "89") (name "/RAS") (class "Default")
      (node (ref "U601") (pin "K6") (pinfunction "~{RAS}_K6") (pintype "input"))
    )
    (net (code "90") (name "/SDA10") (class "Default")
      (node (ref "U601") (pin "N7") (pinfunction "A10_N7") (pintype "input"))
    )
    (net (code "91") (name "/SDCK") (class "Default")
      (node (ref "U601") (pin "K2") (pinfunction "CLK_K2") (pintype "input"))
    )
    (net (code "92") (name "/SDCKE") (class "Default")
      (node (ref "U601") (pin "L1") (pinfunction "CKE_L1") (pintype "input"))
    )
    (net (code "93") (name "/SDCS") (class "Default")
      (node (ref "R604") (pin "2") (pinfunction "2_2") (pintype "passive"))
      (node (ref "U601") (pin "L7") (pinfunction "~{CS}_L7") (pintype "input"))
    )
    (net (code "94") (name "/SDWE") (class "Default")
      (node (ref "U601") (pin "J7") (pinfunction "~{WE}_J7") (pintype "input"))
    )
    (net (code "101") (name "GND") (class "Default")
      (node (ref "C600") (pin "2") (pinfunction "2_2") (pintype "passive"))
      (node (ref "C601") (pin "2") (pinfunction "2_2") (pintype "passive"))
      (node (ref "C602") (pin "2") (pinfunction "2_2") (pintype "passive"))
      (node (ref "C603") (pin "2") (pinfunction "2_2") (pintype "passive"))
      (node (ref "C604") (pin "2") (pinfunction "2_2") (pintype "passive"))
      (node (ref "C605") (pin "2") (pinfunction "2_2") (pintype "passive"))
      (node (ref "C606") (pin "2") (pinfunction "2_2") (pintype "passive"))
      (node (ref "C607") (pin "2") (pinfunction "2_2") (pintype "passive"))
      (node (ref "C608") (pin "2") (pinfunction "2_2") (pintype "passive"))
      (node (ref "C609") (pin "2") (pinfunction "2_2") (pintype "passive"))
      (node (ref "C610") (pin "2") (pinfunction "2_2") (pintype "passive"))
      (node (ref "C611") (pin "2") (pinfunction "2_2") (pintype "passive"))
      (node (ref "C612") (pin "2") (pinfunction "2_2") (pintype "passive"))
      (node (ref "C613") (pin "2") (pinfunction "2_2") (pintype "passive"))
      (node (ref "J600") (pin "11") (pinfunction "COM_11") (pintype "passive"))
      (node (ref "J600") (pin "13") (pinfunction "SHELL_13") (pintype "passive"))
      (node (ref "J600") (pin "14") (pinfunction "SHELL_14") (pintype "passive"))
      (node (ref "J600") (pin "15") (pinfunction "SHELL_15") (pintype "passive"))
      (node (ref "J600") (pin "16") (pinfunction "SHELL_16") (pintype "passive"))
      (node (ref "J600") (pin "3") (pinfunction "VSS1_3") (pintype "passive"))
      (node (ref "J600") (pin "6") (pinfunction "VSS2_6") (pintype "passive"))
      (node (ref "R603") (pin "1") (pinfunction "1_1") (pintype "passive"))
      (node (ref "U600") (pin "4") (pinfunction "GND_4") (pintype "power_in"))
      (node (ref "U601") (pin "A1") (pinfunction "VSS_A1") (pintype "power_in"))
      (node (ref "U601") (pin "B2") (pinfunction "VSSQ_B2") (pintype "power_in"))
      (node (ref "U601") (pin "C6") (pinfunction "VSSQ_C6") (pintype "power_in"))
      (node (ref "U601") (pin "E2") (pinfunction "VSSQ_E2") (pintype "power_in"))
      (node (ref "U601") (pin "F6") (pinfunction "VSSQ_F6") (pintype "power_in"))
      (node (ref "U601") (pin "R1") (pinfunction "VSS_R1") (pintype "power_in"))
      (node (ref "U602") (pin "4") (pinfunction "GND_4") (pintype "power_in"))
      (node (ref "U602") (pin "9") (pinfunction "PAD_9") (pintype "power_in"))
      (node (ref "U603") (pin "4") (pinfunction "GND_4") (pintype "power_in"))
      (node (ref "U604") (pin "4") (pinfunction "VSS_4") (pintype "power_in"))
    )
    (net (code "102") (name "Net-(J600-W{slash}P)") (class "Default")
      (node (ref "J600") (pin "12") (pinfunction "W/P_12") (pintype "passive"))
      (node (ref "R612") (pin "1") (pinfunction "1_1") (pintype "passive"))
      (node (ref "TP600") (pin "1") (pinfunction "1_1") (pintype "passive"))
    )
    (net (code "103") (name "VCC_TARGET_P3V3") (class "Default")
      (node (ref "C600") (pin "1") (pinfunction "1_1") (pintype "passive"))
      (node (ref "C601") (pin "1") (pinfunction "1_1") (pintype "passive"))
      (node (ref "C602") (pin "1") (pinfunction "1_1") (pintype "passive"))
      (node (ref "C603") (pin "1") (pinfunction "1_1") (pintype "passive"))
      (node (ref "C604") (pin "1") (pinfunction "1_1") (pintype "passive"))
      (node (ref "C605") (pin "1") (pinfunction "1_1") (pintype "passive"))
      (node (ref "C606") (pin "1") (pinfunction "1_1") (pintype "passive"))
      (node (ref "C607") (pin "1") (pinfunction "1_1") (pintype "passive"))
      (node (ref "C608") (pin "1") (pinfunction "1_1") (pintype "passive"))
      (node (ref "C609") (pin "1") (pinfunction "1_1") (pintype "passive"))
      (node (ref "C610") (pin "1") (pinfunction "1_1") (pintype "passive"))
      (node (ref "C611") (pin "1") (pinfunction "1_1") (pintype "passive"))
      (node (ref "C612") (pin "1") (pinfunction "1_1") (pintype "passive"))
      (node (ref "C613") (pin "1") (pinfunction "1_1") (pintype "passive"))
      (node (ref "J600") (pin "4") (pinfunction "VDD_4") (pintype "passive"))
      (node (ref "R600") (pin "2") (pinfunction "2_2") (pintype "passive"))
      (node (ref "R601") (pin "2") (pinfunction "2_2") (pintype "passive"))
      (node (ref "R602") (pin "2") (pinfunction "2_2") (pintype "passive"))
      (node (ref "R604") (pin "1") (pinfunction "1_1") (pintype "passive"))
      (node (ref "R605") (pin "1") (pinfunction "1_1") (pintype "passive"))
      (node (ref "R606") (pin "2") (pinfunction "2_2") (pintype "passive"))
      (node (ref "R607") (pin "2") (pinfunction "2_2") (pintype "passive"))
      (node (ref "R608") (pin "2") (pinfunction "2_2") (pintype "passive"))
      (node (ref "R609") (pin "2") (pinfunction "2_2") (pintype "passive"))
      (node (ref "R610") (pin "2") (pinfunction "2_2") (pintype "passive"))
      (node (ref "R611") (pin "2") (pinfunction "2_2") (pintype "passive"))
      (node (ref "R612") (pin "2") (pinfunction "2_2") (pintype "passive"))
      (node (ref "U600") (pin "8") (pinfunction "VCC_8") (pintype "power_in"))
      (node (ref "U601") (pin "A7") (pinfunction "VDD_A7") (pintype "power_in"))
      (node (ref "U601") (pin "B6") (pinfunction "VDDQ_B6") (pintype "power_in"))
      (node (ref "U601") (pin "C2") (pinfunction "VDDQ_C2") (pintype "power_in"))
      (node (ref "U601") (pin "E6") (pinfunction "VDDQ_E6") (pintype "power_in"))
      (node (ref "U601") (pin "F2") (pinfunction "VDDQ_F2") (pintype "power_in"))
      (node (ref "U601") (pin "H6") (pinfunction "VDD_H6") (pintype "power_in"))
      (node (ref "U601") (pin "R7") (pinfunction "VDD_R7") (pintype "power_in"))
      (node (ref "U602") (pin "8") (pinfunction "VCC_8") (pintype "power_in"))
      (node (ref "U603") (pin "8") (pinfunction "VCC_8") (pintype "power_in"))
      (node (ref "U604") (pin "8") (pinfunction "VCC_8") (pintype "power_in"))
    )
    (net (code "104") (name "unconnected-(U602-NC-Pad1)") (class "Default")
      (node (ref "U602") (pin "1") (pinfunction "NC_1") (pintype "passive+no_connect"))
    )
    (net (code "105") (name "unconnected-(U602-NC-Pad2)") (class "Default")
      (node (ref "U602") (pin "2") (pinfunction "NC_2") (pintype "passive+no_connect"))
    )
    (net (code "106") (name "unconnected-(U602-NC-Pad3)") (class "Default")
      (node (ref "U602") (pin "3") (pinfunction "NC_3") (pintype "passive+no_connect"))
    )
    (net (code "107") (name "unconnected-(U602-NC-Pad7)") (class "Default")
      (node (ref "U602") (pin "7") (pinfunction "NC_7") (pintype "passive+no_connect"))
    )
    (net (code "108") (name "unconnected-(U603-NC-Pad1)") (class "Default")
      (node (ref "U603") (pin "1") (pinfunction "NC_1") (pintype "passive+no_connect"))
    )
    (net (code "109") (name "unconnected-(U603-NC-Pad2)") (class "Default")
      (node (ref "U603") (pin "2") (pinfunction "NC_2") (pintype "passive+no_connect"))
    )
    (net (code "110") (name "unconnected-(U603-NC-Pad3)") (class "Default")
      (node (ref "U603") (pin "3") (pinfunction "NC_3") (pintype "passive+no_connect"))
    )
    (net (code "111") (name "unconnected-(U603-NC-Pad7)") (class "Default")
      (node (ref "U603") (pin "7") (pinfunction "NC_7") (pintype "passive+no_connect"))
    )
  )
)
